# porcupine5v1_3.net
KiCad netlist of a schematic drawn in EAGLE
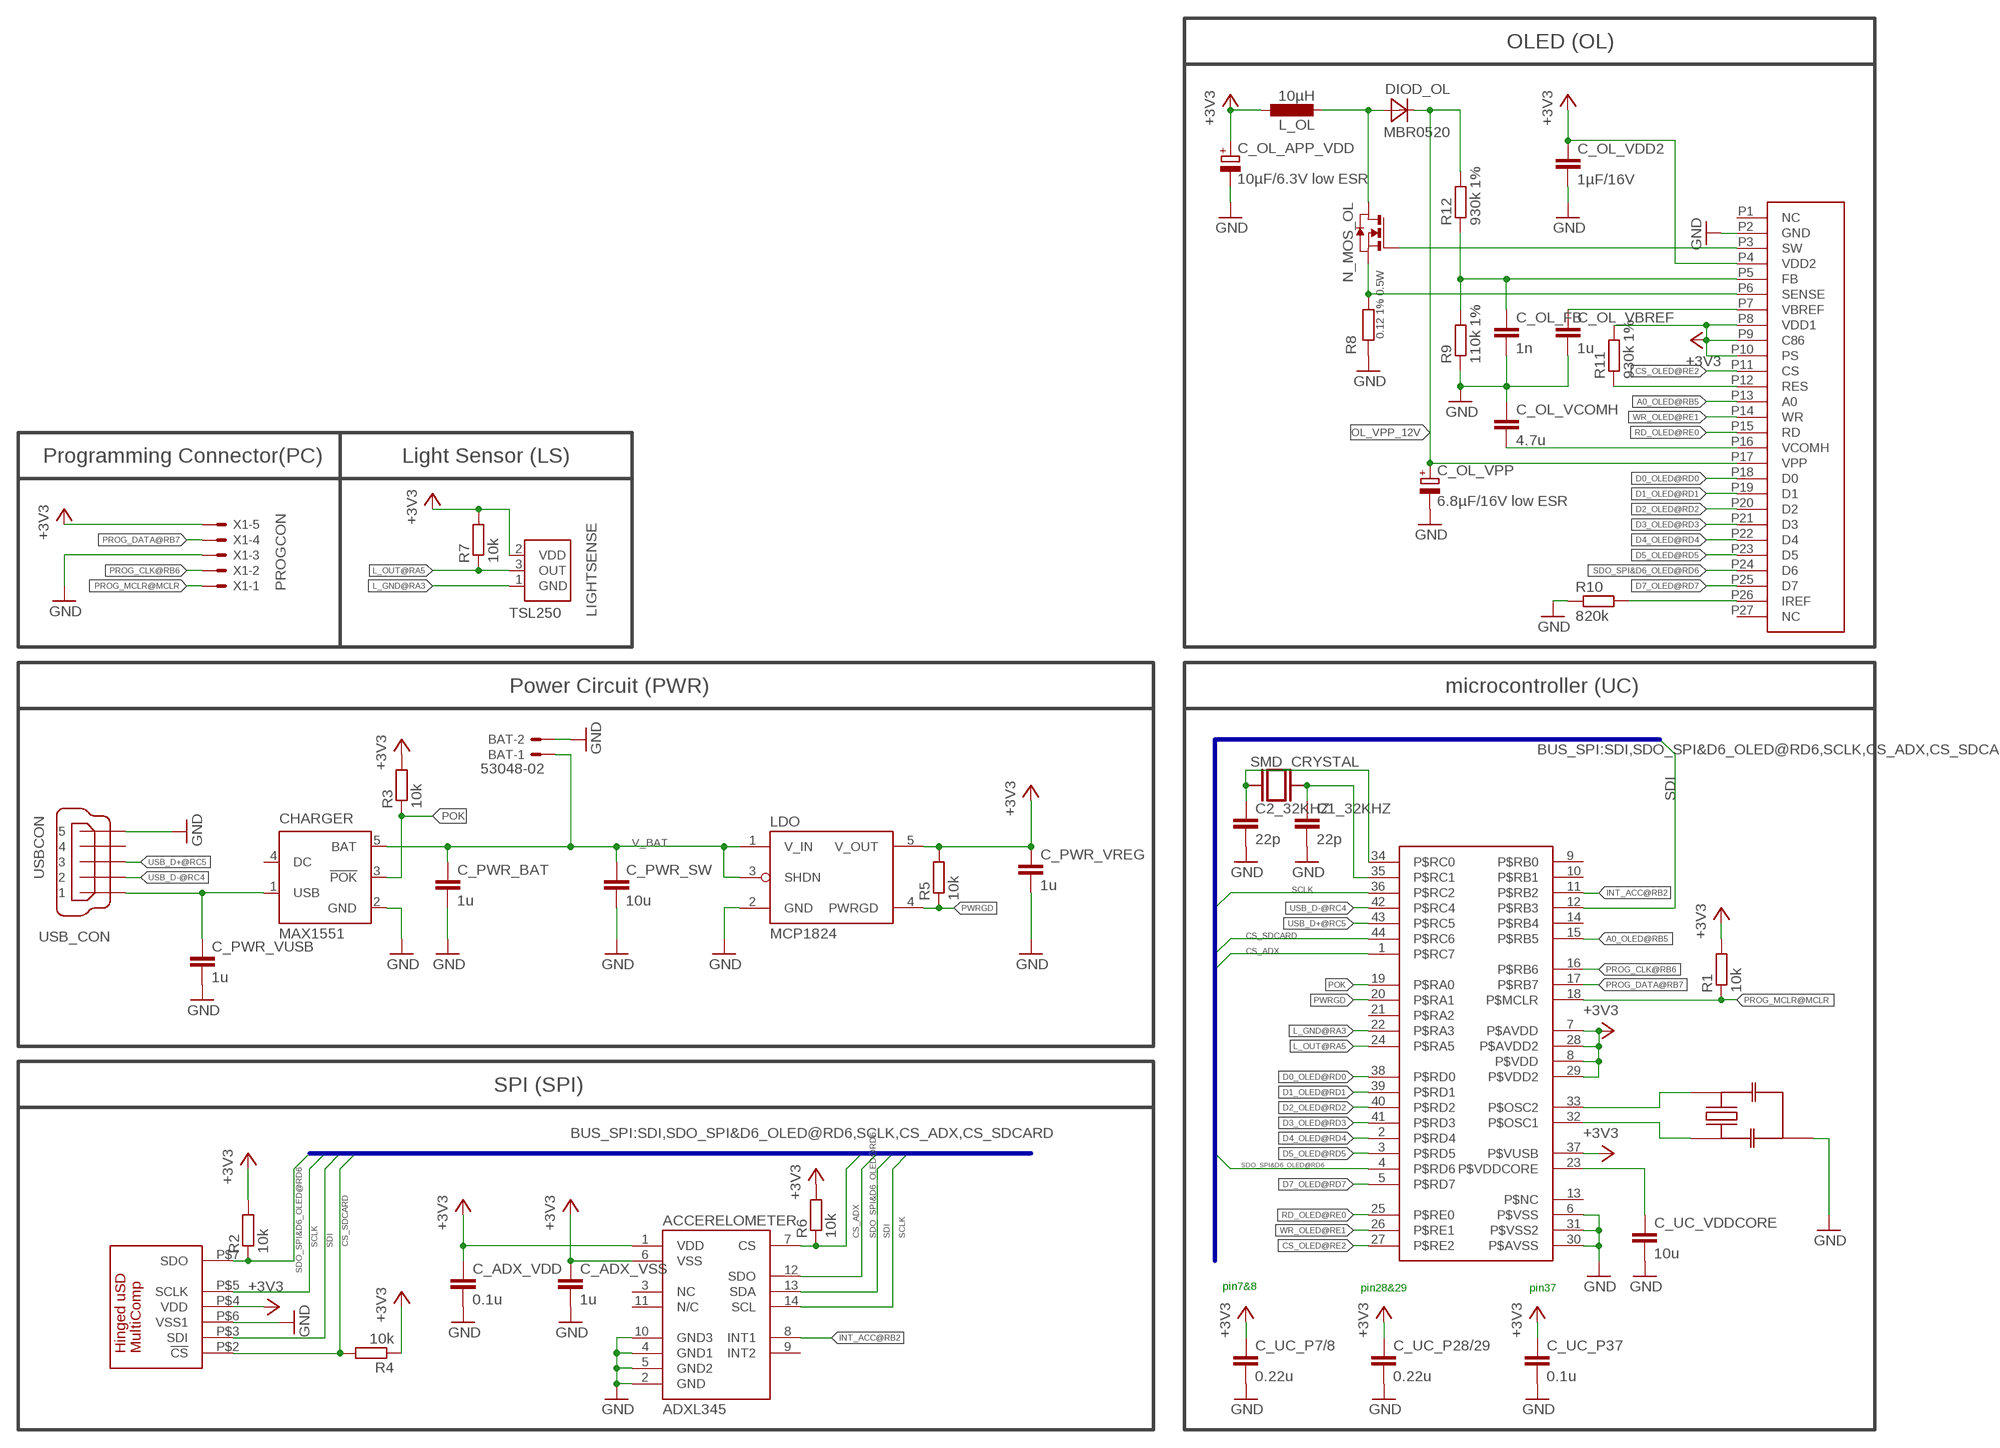
[diagram p0: schematic, sheet 1]

(export (version "E")
  (design (tool "Eeschema 10.0.6"))
  (components
    (comp (ref "ACCERELOMETER")
      (value "ADXL345")
      (footprint "eagle-import:LGA14")
      (libsource (lib "eagle-import") (part "ADXL345"))
    )
    (comp (ref "BAT")
      (value "53048-02")
      (footprint "eagle-import:53048-02")
      (fields (field (name "MF") "MOLEX") (field (name "MPN") "53048-0210"))
      (libsource (lib "eagle-import") (part "53?-02048"))
    )
    (comp (ref "C1_32KHZ")
      (value "22p")
      (footprint "eagle-import:C0603K")
      (libsource (lib "eagle-import") (part "C-EUC0603K"))
    )
    (comp (ref "C2_32KHZ")
      (value "22p")
      (footprint "eagle-import:C0603K")
      (libsource (lib "eagle-import") (part "C-EUC0603K"))
    )
    (comp (ref "CHARGER")
      (value "MAX1551")
      (footprint "eagle-import:SOT23-5L")
      (libsource (lib "eagle-import") (part "MAX1551"))
    )
    (comp (ref "CON_OLED")
      (value "OLED_DENSITRON")
      (footprint "eagle-import:CON_DD-12864WE-1A")
      (libsource (lib "eagle-import") (part "OLED_DENSITRON"))
    )
    (comp (ref "C_ADX_VDD")
      (value "0.1u")
      (footprint "eagle-import:C0603K")
      (libsource (lib "eagle-import") (part "C-EUC0603K"))
    )
    (comp (ref "C_ADX_VSS")
      (value "1u")
      (footprint "eagle-import:C0603K")
      (libsource (lib "eagle-import") (part "C-EUC0603K"))
    )
    (comp (ref "C_OL_APP_VDD")
      (value "10µF/6.3V low ESR")
      (footprint "eagle-import:A_3216-18R")
      (libsource (lib "eagle-import") (part "CPOL-EUA/3216-18R"))
    )
    (comp (ref "C_OL_FB")
      (value "1n")
      (footprint "eagle-import:C0603K")
      (libsource (lib "eagle-import") (part "C-EUC0603K"))
    )
    (comp (ref "C_OL_VBREF")
      (value "1u")
      (footprint "eagle-import:C0603K")
      (libsource (lib "eagle-import") (part "C-EUC0603K"))
    )
    (comp (ref "C_OL_VCOMH")
      (value "4.7u")
      (footprint "eagle-import:C0603K")
      (libsource (lib "eagle-import") (part "C-EUC0603K"))
    )
    (comp (ref "C_OL_VDD2")
      (value "1µF/16V")
      (footprint "eagle-import:C0603K")
      (libsource (lib "eagle-import") (part "C-EUC0603K"))
    )
    (comp (ref "C_OL_VPP")
      (value "6.8µF/16V low ESR")
      (footprint "eagle-import:A_3216-18R")
      (libsource (lib "eagle-import") (part "CPOL-EUA/3216-18R"))
    )
    (comp (ref "C_PWR_BAT")
      (value "1u")
      (footprint "eagle-import:C0603K")
      (libsource (lib "eagle-import") (part "C-EUC0603K"))
    )
    (comp (ref "C_PWR_SW")
      (value "10u")
      (footprint "eagle-import:C0805K")
      (libsource (lib "eagle-import") (part "C-EUC0805K"))
    )
    (comp (ref "C_PWR_VREG")
      (value "1u")
      (footprint "eagle-import:C0603K")
      (libsource (lib "eagle-import") (part "C-EUC0603K"))
    )
    (comp (ref "C_PWR_VUSB")
      (value "1u")
      (footprint "eagle-import:C0603K")
      (libsource (lib "eagle-import") (part "C-EUC0603K"))
    )
    (comp (ref "C_UC_P7/8")
      (value "0.22u")
      (footprint "eagle-import:C0603K")
      (libsource (lib "eagle-import") (part "C-EUC0603K"))
    )
    (comp (ref "C_UC_P28/29")
      (value "0.22u")
      (footprint "eagle-import:C0603K")
      (libsource (lib "eagle-import") (part "C-EUC0603K"))
    )
    (comp (ref "C_UC_P37")
      (value "0.1u")
      (footprint "eagle-import:C0603K")
      (libsource (lib "eagle-import") (part "C-EUC0603K"))
    )
    (comp (ref "C_UC_VDDCORE")
      (value "10u")
      (footprint "eagle-import:C0805K")
      (libsource (lib "eagle-import") (part "C-EUC0805K"))
    )
    (comp (ref "DIOD_OL")
      (value "MBR0520")
      (footprint "eagle-import:SOD123")
      (libsource (lib "eagle-import") (part "MBR0520"))
    )
    (comp (ref "LDO")
      (value "MCP1824")
      (footprint "eagle-import:SOT-23-5")
      (libsource (lib "eagle-import") (part "MCP1824"))
    )
    (comp (ref "LIGHTSENSE")
      (value "TSL250")
      (footprint "eagle-import:TSL")
      (libsource (lib "eagle-import") (part "TSL250"))
    )
    (comp (ref "L_OL")
      (value "10µH")
      (footprint "eagle-import:1212_FOR_INDUCTANCE")
      (libsource (lib "eagle-import") (part "LQH3NP"))
    )
    (comp (ref "N_MOS_OL")
      (value "MGSF1N02LT1")
      (footprint "eagle-import:SOT-23")
      (libsource (lib "eagle-import") (part "MGSF1N02LT1"))
    )
    (comp (ref "PIC_CONTROLLER")
      (value "PIC_P2V6")
      (footprint "eagle-import:QFN44ML8X8")
      (libsource (lib "eagle-import") (part "PIC_P2V6"))
    )
    (comp (ref "R1")
      (value "10k")
      (footprint "eagle-import:R0603")
      (libsource (lib "eagle-import") (part "R-EU_R0603"))
    )
    (comp (ref "R2")
      (value "10k")
      (footprint "eagle-import:R0603")
      (libsource (lib "eagle-import") (part "R-EU_R0603"))
    )
    (comp (ref "R3")
      (value "10k")
      (footprint "eagle-import:R0603")
      (libsource (lib "eagle-import") (part "R-EU_R0603"))
    )
    (comp (ref "R4")
      (value "10k")
      (footprint "eagle-import:R0603")
      (libsource (lib "eagle-import") (part "R-EU_R0603"))
    )
    (comp (ref "R5")
      (value "10k")
      (footprint "eagle-import:R0603")
      (libsource (lib "eagle-import") (part "R-EU_R0603"))
    )
    (comp (ref "R6")
      (value "10k")
      (footprint "eagle-import:R0603")
      (libsource (lib "eagle-import") (part "R-EU_R0603"))
    )
    (comp (ref "R7")
      (value "10k")
      (footprint "eagle-import:R0603")
      (libsource (lib "eagle-import") (part "R-EU_R0603"))
    )
    (comp (ref "R8")
      (value "0.12 1% 0.5W")
      (footprint "eagle-import:0805_UPSIDEDOWN")
      (libsource (lib "eagle-import") (part "RESISTOR_PAN_ERJB3CFR12V"))
    )
    (comp (ref "R9")
      (value "110k 1%")
      (footprint "eagle-import:R0603")
      (libsource (lib "eagle-import") (part "R-EU_R0603"))
    )
    (comp (ref "R10")
      (value "820k")
      (footprint "eagle-import:R0603")
      (libsource (lib "eagle-import") (part "R-EU_R0603"))
    )
    (comp (ref "R11")
      (value "930k 1%")
      (footprint "eagle-import:R0603")
      (libsource (lib "eagle-import") (part "R-EU_R0603"))
    )
    (comp (ref "R12")
      (value "930k 1%")
      (footprint "eagle-import:R0603")
      (libsource (lib "eagle-import") (part "R-EU_R0603"))
    )
    (comp (ref "RESONATOR")
      (value "RESONATORPRQC-S")
      (footprint "eagle-import:PRQC")
      (libsource (lib "eagle-import") (part "RESONATORPRQC-S"))
    )
    (comp (ref "SDCARD_CON")
      (value "MICROSD_CONN")
      (footprint "eagle-import:460DA40013")
      (libsource (lib "eagle-import") (part "MICROSD_CONN"))
    )
    (comp (ref "SMD_CRYSTAL")
      (value "SMD_CRYSTAL")
      (footprint "eagle-import:SMD_CRYSTAL")
      (libsource (lib "eagle-import") (part "SMD_CRYSTAL"))
    )
    (comp (ref "USB_CON")
      (value "USBCON")
      (footprint "eagle-import:248601")
      (libsource (lib "eagle-import") (part "USBCON"))
    )
    (comp (ref "X1")
      (value "PROGCON")
      (footprint "eagle-import:53047-05-OCT")
      (libsource (lib "eagle-import") (part "PROGCON"))
    )
  )
  (nets
    (net (code "2") (name "+3V3") (class "Default")
      (node (ref "ACCERELOMETER") (pin "1") (pinfunction "VDD_1") (pintype "bidirectional"))
      (node (ref "ACCERELOMETER") (pin "6") (pinfunction "VSS_6") (pintype "bidirectional"))
      (node (ref "CON_OLED") (pin "P10") (pinfunction "PS_P10") (pintype "bidirectional"))
      (node (ref "CON_OLED") (pin "P4") (pinfunction "VDD2_P4") (pintype "power_in"))
      (node (ref "CON_OLED") (pin "P8") (pinfunction "VDD1_P8") (pintype "power_in"))
      (node (ref "CON_OLED") (pin "P9") (pinfunction "C86_P9") (pintype "bidirectional"))
      (node (ref "C_ADX_VDD") (pin "1") (pinfunction "1_1") (pintype "passive"))
      (node (ref "C_ADX_VSS") (pin "1") (pinfunction "1_1") (pintype "passive"))
      (node (ref "C_OL_APP_VDD") (pin "+") (pinfunction "+_+") (pintype "passive"))
      (node (ref "C_OL_VDD2") (pin "2") (pinfunction "2_2") (pintype "passive"))
      (node (ref "C_PWR_VREG") (pin "1") (pinfunction "1_1") (pintype "passive"))
      (node (ref "C_UC_P28/29") (pin "1") (pinfunction "1_1") (pintype "passive"))
      (node (ref "C_UC_P37") (pin "1") (pinfunction "1_1") (pintype "passive"))
      (node (ref "C_UC_P7/8") (pin "1") (pinfunction "1_1") (pintype "passive"))
      (node (ref "LDO") (pin "5") (pinfunction "V_OUT_5") (pintype "bidirectional"))
      (node (ref "LIGHTSENSE") (pin "2") (pinfunction "VDD_2") (pintype "power_in"))
      (node (ref "L_OL") (pin "P$1") (pinfunction "1_P$1") (pintype "passive"))
      (node (ref "PIC_CONTROLLER") (pin "28") (pinfunction "P$AVDD2_28") (pintype "bidirectional"))
      (node (ref "PIC_CONTROLLER") (pin "29") (pinfunction "P$VDD2_29") (pintype "bidirectional"))
      (node (ref "PIC_CONTROLLER") (pin "37") (pinfunction "P$VUSB_37") (pintype "bidirectional"))
      (node (ref "PIC_CONTROLLER") (pin "7") (pinfunction "P$AVDD_7") (pintype "input"))
      (node (ref "PIC_CONTROLLER") (pin "8") (pinfunction "P$VDD_8") (pintype "bidirectional"))
      (node (ref "R1") (pin "2") (pinfunction "2_2") (pintype "passive"))
      (node (ref "R11") (pin "2") (pinfunction "2_2") (pintype "passive"))
      (node (ref "R2") (pin "2") (pinfunction "2_2") (pintype "passive"))
      (node (ref "R3") (pin "2") (pinfunction "2_2") (pintype "passive"))
      (node (ref "R4") (pin "1") (pinfunction "1_1") (pintype "passive"))
      (node (ref "R5") (pin "2") (pinfunction "2_2") (pintype "passive"))
      (node (ref "R6") (pin "2") (pinfunction "2_2") (pintype "passive"))
      (node (ref "R7") (pin "2") (pinfunction "2_2") (pintype "passive"))
      (node (ref "SDCARD_CON") (pin "P$4") (pinfunction "VDD_P$4") (pintype "bidirectional"))
      (node (ref "X1") (pin "5") (pinfunction "S_5") (pintype "passive"))
    )
    (net (code "3") (name "/CS_ADX") (class "Default")
      (node (ref "ACCERELOMETER") (pin "7") (pinfunction "CS_7") (pintype "bidirectional"))
      (node (ref "PIC_CONTROLLER") (pin "1") (pinfunction "P$RC7_1") (pintype "bidirectional"))
      (node (ref "R6") (pin "1") (pinfunction "1_1") (pintype "passive"))
    )
    (net (code "4") (name "/CS_SDCARD") (class "Default")
      (node (ref "PIC_CONTROLLER") (pin "44") (pinfunction "P$RC6_44") (pintype "bidirectional"))
      (node (ref "R4") (pin "2") (pinfunction "2_2") (pintype "passive"))
      (node (ref "SDCARD_CON") (pin "P$2") (pinfunction "~{CS}_P$2") (pintype "bidirectional"))
    )
    (net (code "5") (name "/SCLK") (class "Default")
      (node (ref "ACCERELOMETER") (pin "14") (pinfunction "SCL_14") (pintype "bidirectional"))
      (node (ref "PIC_CONTROLLER") (pin "36") (pinfunction "P$RC2_36") (pintype "bidirectional"))
      (node (ref "SDCARD_CON") (pin "P$5") (pinfunction "SCLK_P$5") (pintype "bidirectional"))
    )
    (net (code "6") (name "/SDI") (class "Default")
      (node (ref "ACCERELOMETER") (pin "13") (pinfunction "SDA_13") (pintype "bidirectional"))
      (node (ref "PIC_CONTROLLER") (pin "12") (pinfunction "P$RB3_12") (pintype "bidirectional"))
      (node (ref "SDCARD_CON") (pin "P$3") (pinfunction "SDI_P$3") (pintype "bidirectional"))
    )
    (net (code "7") (name "/V_BAT") (class "Default")
      (node (ref "BAT") (pin "1") (pinfunction "S_1") (pintype "passive"))
      (node (ref "CHARGER") (pin "5") (pinfunction "BAT_5") (pintype "passive"))
      (node (ref "C_PWR_BAT") (pin "1") (pinfunction "1_1") (pintype "passive"))
      (node (ref "C_PWR_SW") (pin "1") (pinfunction "1_1") (pintype "passive"))
      (node (ref "LDO") (pin "1") (pinfunction "V_IN_1") (pintype "bidirectional"))
      (node (ref "LDO") (pin "3") (pinfunction "SHDN_3") (pintype "bidirectional"))
    )
    (net (code "9") (name "A0_OLED@RB5") (class "Default")
      (node (ref "CON_OLED") (pin "P13") (pinfunction "A0_P13") (pintype "bidirectional"))
      (node (ref "PIC_CONTROLLER") (pin "15") (pinfunction "P$RB5_15") (pintype "bidirectional"))
    )
    (net (code "10") (name "CS_OLED@RE2") (class "Default")
      (node (ref "CON_OLED") (pin "P11") (pinfunction "CS_P11") (pintype "bidirectional"))
      (node (ref "PIC_CONTROLLER") (pin "27") (pinfunction "P$RE2_27") (pintype "bidirectional"))
    )
    (net (code "11") (name "D0_OLED@RD0") (class "Default")
      (node (ref "CON_OLED") (pin "P18") (pinfunction "D0_P18") (pintype "bidirectional"))
      (node (ref "PIC_CONTROLLER") (pin "38") (pinfunction "P$RD0_38") (pintype "bidirectional"))
    )
    (net (code "12") (name "D1_OLED@RD1") (class "Default")
      (node (ref "CON_OLED") (pin "P19") (pinfunction "D1_P19") (pintype "bidirectional"))
      (node (ref "PIC_CONTROLLER") (pin "39") (pinfunction "P$RD1_39") (pintype "bidirectional"))
    )
    (net (code "13") (name "D2_OLED@RD2") (class "Default")
      (node (ref "CON_OLED") (pin "P20") (pinfunction "D2_P20") (pintype "bidirectional"))
      (node (ref "PIC_CONTROLLER") (pin "40") (pinfunction "P$RD2_40") (pintype "bidirectional"))
    )
    (net (code "14") (name "D3_OLED@RD3") (class "Default")
      (node (ref "CON_OLED") (pin "P21") (pinfunction "D3_P21") (pintype "bidirectional"))
      (node (ref "PIC_CONTROLLER") (pin "41") (pinfunction "P$RD3_41") (pintype "bidirectional"))
    )
    (net (code "15") (name "D4_OLED@RD4") (class "Default")
      (node (ref "CON_OLED") (pin "P22") (pinfunction "D4_P22") (pintype "bidirectional"))
      (node (ref "PIC_CONTROLLER") (pin "2") (pinfunction "P$RD4_2") (pintype "bidirectional"))
    )
    (net (code "16") (name "D5_OLED@RD5") (class "Default")
      (node (ref "CON_OLED") (pin "P23") (pinfunction "D5_P23") (pintype "bidirectional"))
      (node (ref "PIC_CONTROLLER") (pin "3") (pinfunction "P$RD5_3") (pintype "power_in"))
    )
    (net (code "17") (name "D7_OLED@RD7") (class "Default")
      (node (ref "CON_OLED") (pin "P25") (pinfunction "D7_P25") (pintype "bidirectional"))
      (node (ref "PIC_CONTROLLER") (pin "5") (pinfunction "P$RD7_5") (pintype "power_in"))
    )
    (net (code "18") (name "GND") (class "Default")
      (node (ref "ACCERELOMETER") (pin "10") (pinfunction "GND3_10") (pintype "bidirectional"))
      (node (ref "ACCERELOMETER") (pin "2") (pinfunction "GND_2") (pintype "bidirectional"))
      (node (ref "ACCERELOMETER") (pin "4") (pinfunction "GND1_4") (pintype "bidirectional"))
      (node (ref "ACCERELOMETER") (pin "5") (pinfunction "GND2_5") (pintype "bidirectional"))
      (node (ref "BAT") (pin "2") (pinfunction "S_2") (pintype "passive"))
      (node (ref "C1_32KHZ") (pin "2") (pinfunction "2_2") (pintype "passive"))
      (node (ref "C2_32KHZ") (pin "2") (pinfunction "2_2") (pintype "passive"))
      (node (ref "CHARGER") (pin "2") (pinfunction "GND_2") (pintype "power_in"))
      (node (ref "CON_OLED") (pin "P2") (pinfunction "GND_P2") (pintype "power_in"))
      (node (ref "C_ADX_VDD") (pin "2") (pinfunction "2_2") (pintype "passive"))
      (node (ref "C_ADX_VSS") (pin "2") (pinfunction "2_2") (pintype "passive"))
      (node (ref "C_OL_APP_VDD") (pin "-") (pinfunction "-_-") (pintype "passive"))
      (node (ref "C_OL_FB") (pin "2") (pinfunction "2_2") (pintype "passive"))
      (node (ref "C_OL_VBREF") (pin "2") (pinfunction "2_2") (pintype "passive"))
      (node (ref "C_OL_VCOMH") (pin "1") (pinfunction "1_1") (pintype "passive"))
      (node (ref "C_OL_VDD2") (pin "1") (pinfunction "1_1") (pintype "passive"))
      (node (ref "C_OL_VPP") (pin "-") (pinfunction "-_-") (pintype "passive"))
      (node (ref "C_PWR_BAT") (pin "2") (pinfunction "2_2") (pintype "passive"))
      (node (ref "C_PWR_SW") (pin "2") (pinfunction "2_2") (pintype "passive"))
      (node (ref "C_PWR_VREG") (pin "2") (pinfunction "2_2") (pintype "passive"))
      (node (ref "C_PWR_VUSB") (pin "2") (pinfunction "2_2") (pintype "passive"))
      (node (ref "C_UC_P28/29") (pin "2") (pinfunction "2_2") (pintype "passive"))
      (node (ref "C_UC_P37") (pin "2") (pinfunction "2_2") (pintype "passive"))
      (node (ref "C_UC_P7/8") (pin "2") (pinfunction "2_2") (pintype "passive"))
      (node (ref "C_UC_VDDCORE") (pin "2") (pinfunction "2_2") (pintype "passive"))
      (node (ref "LDO") (pin "2") (pinfunction "GND_2") (pintype "bidirectional"))
      (node (ref "PIC_CONTROLLER") (pin "30") (pinfunction "P$AVSS_30") (pintype "input"))
      (node (ref "PIC_CONTROLLER") (pin "31") (pinfunction "P$VSS2_31") (pintype "output"))
      (node (ref "PIC_CONTROLLER") (pin "6") (pinfunction "P$VSS_6") (pintype "input"))
      (node (ref "R10") (pin "1") (pinfunction "1_1") (pintype "passive"))
      (node (ref "R8") (pin "P$2") (pinfunction "1_P$2") (pintype "passive"))
      (node (ref "R9") (pin "1") (pinfunction "1_1") (pintype "passive"))
      (node (ref "RESONATOR") (pin "GND") (pinfunction "GND_GND") (pintype "bidirectional"))
      (node (ref "SDCARD_CON") (pin "P$6") (pinfunction "VSS1_P$6") (pintype "bidirectional"))
      (node (ref "USB_CON") (pin "5") (pinfunction "5_5") (pintype "input"))
      (node (ref "X1") (pin "3") (pinfunction "S_3") (pintype "passive"))
    )
    (net (code "19") (name "INT_ACC@RB2") (class "Default")
      (node (ref "ACCERELOMETER") (pin "8") (pinfunction "INT1_8") (pintype "bidirectional"))
      (node (ref "PIC_CONTROLLER") (pin "11") (pinfunction "P$RB2_11") (pintype "power_in"))
    )
    (net (code "20") (name "L_GND@RA3") (class "Default")
      (node (ref "LIGHTSENSE") (pin "1") (pinfunction "GND_1") (pintype "power_in"))
      (node (ref "PIC_CONTROLLER") (pin "22") (pinfunction "P$RA3_22") (pintype "bidirectional"))
    )
    (net (code "21") (name "L_OUT@RA5") (class "Default")
      (node (ref "LIGHTSENSE") (pin "3") (pinfunction "OUT_3") (pintype "output"))
      (node (ref "PIC_CONTROLLER") (pin "24") (pinfunction "P$RA5_24") (pintype "bidirectional"))
      (node (ref "R7") (pin "1") (pinfunction "1_1") (pintype "passive"))
    )
    (net (code "22") (name "Net-(CHARGER-USB)") (class "Default")
      (node (ref "CHARGER") (pin "1") (pinfunction "USB_1") (pintype "input"))
      (node (ref "C_PWR_VUSB") (pin "1") (pinfunction "1_1") (pintype "passive"))
      (node (ref "USB_CON") (pin "1") (pinfunction "1_1") (pintype "input"))
    )
    (net (code "23") (name "Net-(CON_OLED-FB)") (class "Default")
      (node (ref "CON_OLED") (pin "P5") (pinfunction "FB_P5") (pintype "bidirectional"))
      (node (ref "C_OL_FB") (pin "1") (pinfunction "1_1") (pintype "passive"))
      (node (ref "R12") (pin "1") (pinfunction "1_1") (pintype "passive"))
      (node (ref "R9") (pin "2") (pinfunction "2_2") (pintype "passive"))
    )
    (net (code "24") (name "Net-(CON_OLED-IREF)") (class "Default")
      (node (ref "CON_OLED") (pin "P26") (pinfunction "IREF_P26") (pintype "bidirectional"))
      (node (ref "R10") (pin "2") (pinfunction "2_2") (pintype "passive"))
    )
    (net (code "25") (name "Net-(CON_OLED-RES)") (class "Default")
      (node (ref "CON_OLED") (pin "P12") (pinfunction "RES_P12") (pintype "bidirectional"))
      (node (ref "R11") (pin "1") (pinfunction "1_1") (pintype "passive"))
    )
    (net (code "26") (name "Net-(CON_OLED-SENSE)") (class "Default")
      (node (ref "CON_OLED") (pin "P6") (pinfunction "SENSE_P6") (pintype "bidirectional"))
      (node (ref "N_MOS_OL") (pin "2") (pinfunction "S_2") (pintype "passive"))
      (node (ref "R8") (pin "P$3") (pinfunction "2_P$3") (pintype "passive"))
    )
    (net (code "27") (name "Net-(CON_OLED-SW)") (class "Default")
      (node (ref "CON_OLED") (pin "P3") (pinfunction "SW_P3") (pintype "bidirectional"))
      (node (ref "N_MOS_OL") (pin "3") (pinfunction "G_3") (pintype "passive"))
    )
    (net (code "28") (name "Net-(CON_OLED-VBREF)") (class "Default")
      (node (ref "CON_OLED") (pin "P7") (pinfunction "VBREF_P7") (pintype "bidirectional"))
      (node (ref "C_OL_VBREF") (pin "1") (pinfunction "1_1") (pintype "passive"))
    )
    (net (code "29") (name "Net-(CON_OLED-VCOMH)") (class "Default")
      (node (ref "CON_OLED") (pin "P16") (pinfunction "VCOMH_P16") (pintype "bidirectional"))
      (node (ref "C_OL_VCOMH") (pin "2") (pinfunction "2_2") (pintype "passive"))
    )
    (net (code "30") (name "Net-(L_OL-2)") (class "Default")
      (node (ref "DIOD_OL") (pin "A") (pinfunction "A_A") (pintype "passive"))
      (node (ref "L_OL") (pin "P$2") (pinfunction "2_P$2") (pintype "passive"))
      (node (ref "N_MOS_OL") (pin "1") (pinfunction "D_1") (pintype "passive"))
    )
    (net (code "31") (name "Net-(PIC_CONTROLLER-P$OSC1)") (class "Default")
      (node (ref "PIC_CONTROLLER") (pin "32") (pinfunction "P$OSC1_32") (pintype "bidirectional"))
      (node (ref "RESONATOR") (pin "2") (pinfunction "2_2") (pintype "bidirectional"))
    )
    (net (code "32") (name "Net-(PIC_CONTROLLER-P$OSC2)") (class "Default")
      (node (ref "PIC_CONTROLLER") (pin "33") (pinfunction "P$OSC2_33") (pintype "bidirectional"))
      (node (ref "RESONATOR") (pin "1") (pinfunction "1_1") (pintype "bidirectional"))
    )
    (net (code "33") (name "Net-(PIC_CONTROLLER-P$RC0)") (class "Default")
      (node (ref "C2_32KHZ") (pin "1") (pinfunction "1_1") (pintype "passive"))
      (node (ref "PIC_CONTROLLER") (pin "34") (pinfunction "P$RC0_34") (pintype "bidirectional"))
      (node (ref "SMD_CRYSTAL") (pin "P$1") (pinfunction "1_P$1") (pintype "passive"))
    )
    (net (code "34") (name "Net-(PIC_CONTROLLER-P$RC1)") (class "Default")
      (node (ref "C1_32KHZ") (pin "1") (pinfunction "1_1") (pintype "passive"))
      (node (ref "PIC_CONTROLLER") (pin "35") (pinfunction "P$RC1_35") (pintype "bidirectional"))
      (node (ref "SMD_CRYSTAL") (pin "P$2") (pinfunction "2_P$2") (pintype "passive"))
    )
    (net (code "35") (name "Net-(PIC_CONTROLLER-P$VDDCORE)") (class "Default")
      (node (ref "C_UC_VDDCORE") (pin "1") (pinfunction "1_1") (pintype "passive"))
      (node (ref "PIC_CONTROLLER") (pin "23") (pinfunction "P$VDDCORE_23") (pintype "bidirectional"))
    )
    (net (code "36") (name "OL_VPP_12V") (class "Default")
      (node (ref "CON_OLED") (pin "P17") (pinfunction "VPP_P17") (pintype "bidirectional"))
      (node (ref "C_OL_VPP") (pin "+") (pinfunction "+_+") (pintype "passive"))
      (node (ref "DIOD_OL") (pin "C") (pinfunction "C_C") (pintype "passive"))
      (node (ref "R12") (pin "2") (pinfunction "2_2") (pintype "passive"))
    )
    (net (code "37") (name "POK") (class "Default")
      (node (ref "CHARGER") (pin "3") (pinfunction "~{POK}_3") (pintype "output"))
      (node (ref "PIC_CONTROLLER") (pin "19") (pinfunction "P$RA0_19") (pintype "bidirectional"))
      (node (ref "R3") (pin "1") (pinfunction "1_1") (pintype "passive"))
    )
    (net (code "38") (name "PROG_CLK@RB6") (class "Default")
      (node (ref "PIC_CONTROLLER") (pin "16") (pinfunction "P$RB6_16") (pintype "power_in"))
      (node (ref "X1") (pin "2") (pinfunction "S_2") (pintype "passive"))
    )
    (net (code "39") (name "PROG_DATA@RB7") (class "Default")
      (node (ref "PIC_CONTROLLER") (pin "17") (pinfunction "P$RB7_17") (pintype "power_in"))
      (node (ref "X1") (pin "4") (pinfunction "S_4") (pintype "passive"))
    )
    (net (code "40") (name "PROG_MCLR@MCLR") (class "Default")
      (node (ref "PIC_CONTROLLER") (pin "18") (pinfunction "P$MCLR_18") (pintype "input"))
      (node (ref "R1") (pin "1") (pinfunction "1_1") (pintype "passive"))
      (node (ref "X1") (pin "1") (pinfunction "S_1") (pintype "passive"))
    )
    (net (code "41") (name "PWRGD") (class "Default")
      (node (ref "LDO") (pin "4") (pinfunction "PWRGD_4") (pintype "bidirectional"))
      (node (ref "PIC_CONTROLLER") (pin "20") (pinfunction "P$RA1_20") (pintype "bidirectional"))
      (node (ref "R5") (pin "1") (pinfunction "1_1") (pintype "passive"))
    )
    (net (code "42") (name "RD_OLED@RE0") (class "Default")
      (node (ref "CON_OLED") (pin "P15") (pinfunction "RD_P15") (pintype "bidirectional"))
      (node (ref "PIC_CONTROLLER") (pin "25") (pinfunction "P$RE0_25") (pintype "bidirectional"))
    )
    (net (code "43") (name "SDO_SPI&D6_OLED@RD6") (class "Default")
      (node (ref "ACCERELOMETER") (pin "12") (pinfunction "SDO_12") (pintype "bidirectional"))
      (node (ref "CON_OLED") (pin "P24") (pinfunction "D6_P24") (pintype "bidirectional"))
      (node (ref "PIC_CONTROLLER") (pin "4") (pinfunction "P$RD6_4") (pintype "bidirectional"))
      (node (ref "R2") (pin "1") (pinfunction "1_1") (pintype "passive"))
      (node (ref "SDCARD_CON") (pin "P$7") (pinfunction "SDO_P$7") (pintype "bidirectional"))
    )
    (net (code "44") (name "USB_D+@RC5") (class "Default")
      (node (ref "PIC_CONTROLLER") (pin "43") (pinfunction "P$RC5_43") (pintype "bidirectional"))
      (node (ref "USB_CON") (pin "3") (pinfunction "3_3") (pintype "input"))
    )
    (net (code "45") (name "USB_D-@RC4") (class "Default")
      (node (ref "PIC_CONTROLLER") (pin "42") (pinfunction "P$RC4_42") (pintype "bidirectional"))
      (node (ref "USB_CON") (pin "2") (pinfunction "2_2") (pintype "input"))
    )
    (net (code "46") (name "WR_OLED@RE1") (class "Default")
      (node (ref "CON_OLED") (pin "P14") (pinfunction "WR_P14") (pintype "bidirectional"))
      (node (ref "PIC_CONTROLLER") (pin "26") (pinfunction "P$RE1_26") (pintype "input"))
    )
    (net (code "47") (name "unconnected-(ACCERELOMETER-INT2-Pad9)") (class "Default")
      (node (ref "ACCERELOMETER") (pin "9") (pinfunction "INT2_9") (pintype "bidirectional"))
    )
    (net (code "48") (name "unconnected-(ACCERELOMETER-NC-Pad3)") (class "Default")
      (node (ref "ACCERELOMETER") (pin "3") (pinfunction "NC_3") (pintype "bidirectional"))
    )
    (net (code "49") (name "unconnected-(ACCERELOMETER-N{slash}C-Pad11)") (class "Default")
      (node (ref "ACCERELOMETER") (pin "11") (pinfunction "N/C_11") (pintype "bidirectional"))
    )
    (net (code "50") (name "unconnected-(CHARGER-DC-Pad4)") (class "Default")
      (node (ref "CHARGER") (pin "4") (pinfunction "DC_4") (pintype "input"))
    )
    (net (code "51") (name "unconnected-(CON_OLED-NC-PadP1)") (class "Default")
      (node (ref "CON_OLED") (pin "P1") (pinfunction "NC_P1") (pintype "bidirectional"))
    )
    (net (code "52") (name "unconnected-(CON_OLED-NC-PadP27)") (class "Default")
      (node (ref "CON_OLED") (pin "P27") (pinfunction "NC_P27") (pintype "bidirectional"))
    )
    (net (code "53") (name "unconnected-(PIC_CONTROLLER-P$NC-Pad13)") (class "Default")
      (node (ref "PIC_CONTROLLER") (pin "13") (pinfunction "P$NC_13") (pintype "bidirectional"))
    )
    (net (code "54") (name "unconnected-(PIC_CONTROLLER-P$RA2-Pad21)") (class "Default")
      (node (ref "PIC_CONTROLLER") (pin "21") (pinfunction "P$RA2_21") (pintype "bidirectional"))
    )
    (net (code "55") (name "unconnected-(PIC_CONTROLLER-P$RB0-Pad9)") (class "Default")
      (node (ref "PIC_CONTROLLER") (pin "9") (pinfunction "P$RB0_9") (pintype "bidirectional"))
    )
    (net (code "56") (name "unconnected-(PIC_CONTROLLER-P$RB1-Pad10)") (class "Default")
      (node (ref "PIC_CONTROLLER") (pin "10") (pinfunction "P$RB1_10") (pintype "bidirectional"))
    )
    (net (code "57") (name "unconnected-(PIC_CONTROLLER-P$RB4-Pad14)") (class "Default")
      (node (ref "PIC_CONTROLLER") (pin "14") (pinfunction "P$RB4_14") (pintype "bidirectional"))
    )
    (net (code "58") (name "unconnected-(USB_CON-Pad4)") (class "Default")
      (node (ref "USB_CON") (pin "4") (pinfunction "4_4") (pintype "input"))
    )
  )
)
